# RAM_MUX4_top.net
KiCad netlist of a schematic drawn in Altium Designer
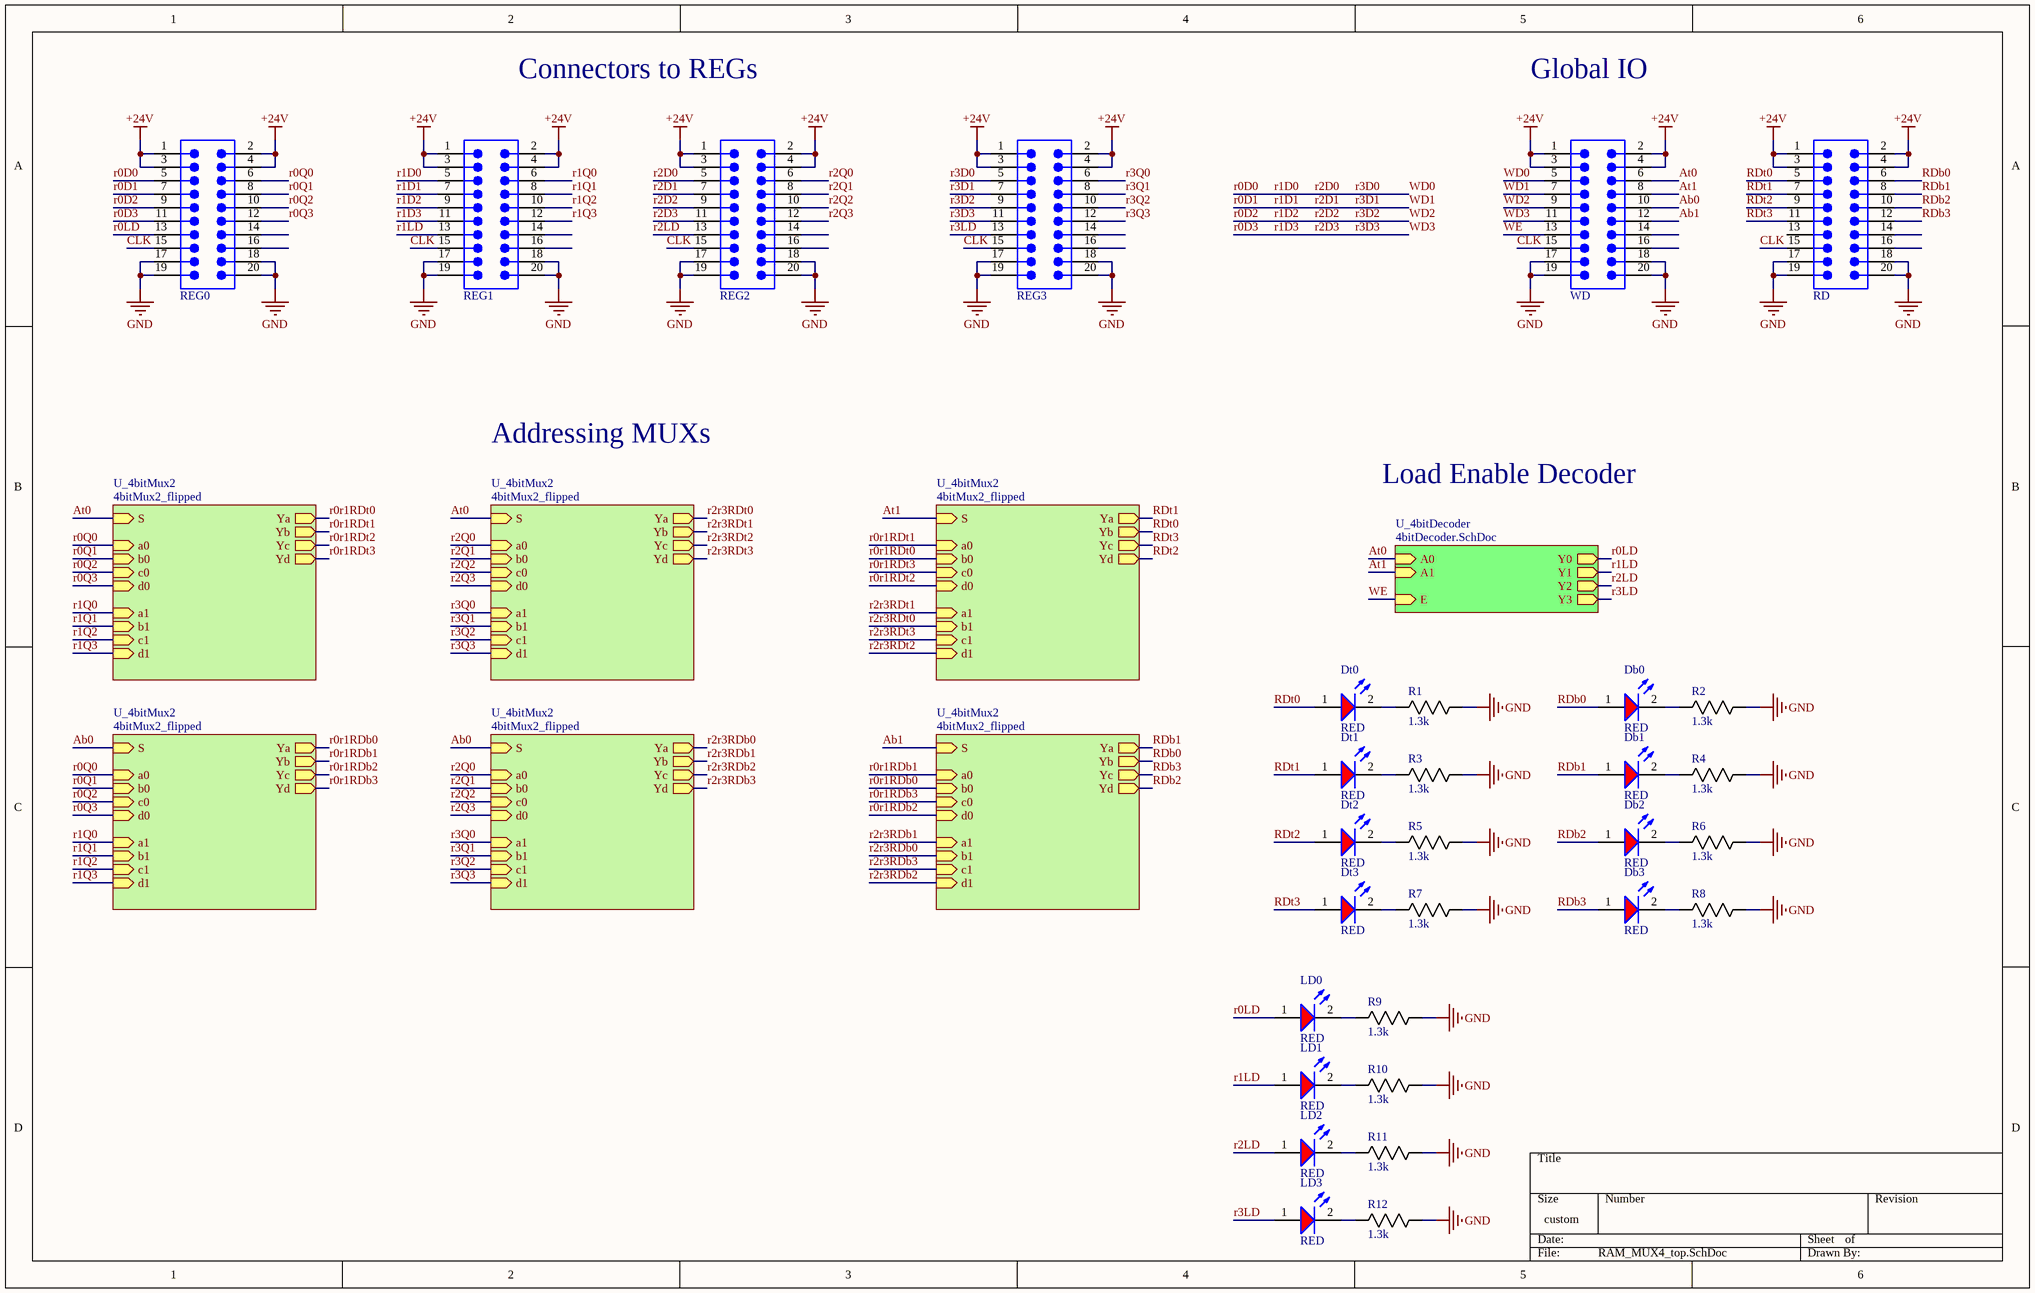
[diagram p0: RAM_MUX4_top.SchDoc]

(export (version "E")
  (design (tool "Eeschema 10.0.6"))
  (components
    (comp (ref "Db0")
      (value "RED")
      (footprint "LED RED 151051RS11000")
      (description "WL-TMRC Red Color Diffused 5 mm Round Through Hole LED")
      (fields
        (field (name "MANUFACTURER") "Wurth Elektronik")
        (field (name "MANUFACTURER PART NUMBER") "151051RS11000")
      )
      (libsource (lib "Schlib1") (part "LED RED 151051RS11000"))
    )
    (comp (ref "Db1")
      (value "RED")
      (footprint "LED RED 151051RS11000")
      (description "WL-TMRC Red Color Diffused 5 mm Round Through Hole LED")
      (fields
        (field (name "MANUFACTURER") "Wurth Elektronik")
        (field (name "MANUFACTURER PART NUMBER") "151051RS11000")
      )
      (libsource (lib "Schlib1") (part "LED RED 151051RS11000"))
    )
    (comp (ref "Db2")
      (value "RED")
      (footprint "LED RED 151051RS11000")
      (description "WL-TMRC Red Color Diffused 5 mm Round Through Hole LED")
      (fields
        (field (name "MANUFACTURER") "Wurth Elektronik")
        (field (name "MANUFACTURER PART NUMBER") "151051RS11000")
      )
      (libsource (lib "Schlib1") (part "LED RED 151051RS11000"))
    )
    (comp (ref "Db3")
      (value "RED")
      (footprint "LED RED 151051RS11000")
      (description "WL-TMRC Red Color Diffused 5 mm Round Through Hole LED")
      (fields
        (field (name "MANUFACTURER") "Wurth Elektronik")
        (field (name "MANUFACTURER PART NUMBER") "151051RS11000")
      )
      (libsource (lib "Schlib1") (part "LED RED 151051RS11000"))
    )
    (comp (ref "Dt0")
      (value "RED")
      (footprint "LED RED 151051RS11000")
      (description "WL-TMRC Red Color Diffused 5 mm Round Through Hole LED")
      (fields
        (field (name "MANUFACTURER") "Wurth Elektronik")
        (field (name "MANUFACTURER PART NUMBER") "151051RS11000")
      )
      (libsource (lib "Schlib1") (part "LED RED 151051RS11000"))
    )
    (comp (ref "Dt1")
      (value "RED")
      (footprint "LED RED 151051RS11000")
      (description "WL-TMRC Red Color Diffused 5 mm Round Through Hole LED")
      (fields
        (field (name "MANUFACTURER") "Wurth Elektronik")
        (field (name "MANUFACTURER PART NUMBER") "151051RS11000")
      )
      (libsource (lib "Schlib1") (part "LED RED 151051RS11000"))
    )
    (comp (ref "Dt2")
      (value "RED")
      (footprint "LED RED 151051RS11000")
      (description "WL-TMRC Red Color Diffused 5 mm Round Through Hole LED")
      (fields
        (field (name "MANUFACTURER") "Wurth Elektronik")
        (field (name "MANUFACTURER PART NUMBER") "151051RS11000")
      )
      (libsource (lib "Schlib1") (part "LED RED 151051RS11000"))
    )
    (comp (ref "Dt3")
      (value "RED")
      (footprint "LED RED 151051RS11000")
      (description "WL-TMRC Red Color Diffused 5 mm Round Through Hole LED")
      (fields
        (field (name "MANUFACTURER") "Wurth Elektronik")
        (field (name "MANUFACTURER PART NUMBER") "151051RS11000")
      )
      (libsource (lib "Schlib1") (part "LED RED 151051RS11000"))
    )
    (comp (ref "LD0")
      (value "RED")
      (footprint "LED RED 151051RS11000")
      (description "WL-TMRC Red Color Diffused 5 mm Round Through Hole LED")
      (fields
        (field (name "MANUFACTURER") "Wurth Elektronik")
        (field (name "MANUFACTURER PART NUMBER") "151051RS11000")
      )
      (libsource (lib "Schlib1") (part "LED RED 151051RS11000"))
    )
    (comp (ref "LD1")
      (value "RED")
      (footprint "LED RED 151051RS11000")
      (description "WL-TMRC Red Color Diffused 5 mm Round Through Hole LED")
      (fields
        (field (name "MANUFACTURER") "Wurth Elektronik")
        (field (name "MANUFACTURER PART NUMBER") "151051RS11000")
      )
      (libsource (lib "Schlib1") (part "LED RED 151051RS11000"))
    )
    (comp (ref "LD2")
      (value "RED")
      (footprint "LED RED 151051RS11000")
      (description "WL-TMRC Red Color Diffused 5 mm Round Through Hole LED")
      (fields
        (field (name "MANUFACTURER") "Wurth Elektronik")
        (field (name "MANUFACTURER PART NUMBER") "151051RS11000")
      )
      (libsource (lib "Schlib1") (part "LED RED 151051RS11000"))
    )
    (comp (ref "LD3")
      (value "RED")
      (footprint "LED RED 151051RS11000")
      (description "WL-TMRC Red Color Diffused 5 mm Round Through Hole LED")
      (fields
        (field (name "MANUFACTURER") "Wurth Elektronik")
        (field (name "MANUFACTURER PART NUMBER") "151051RS11000")
      )
      (libsource (lib "Schlib1") (part "LED RED 151051RS11000"))
    )
    (comp (ref "R1")
      (value "1.3k")
      (footprint "RES 2512")
      (description "Res Thick Film 2512 1.3K Ohm 1% 1W ±100ppm/C Pad SMD Automotive T/R RMCF2512FT1K30")
      (fields
        (field (name "MANUFACTURER") "Stackpole Electronics")
        (field (name "MANUFACTURER PART NUMBER") "RMCF2512FT1K30")
      )
      (libsource (lib "Schlib1") (part "RES 1.3k 2512 1W"))
    )
    (comp (ref "R2")
      (value "1.3k")
      (footprint "RES 2512")
      (description "Res Thick Film 2512 1.3K Ohm 1% 1W ±100ppm/C Pad SMD Automotive T/R RMCF2512FT1K30")
      (fields
        (field (name "MANUFACTURER") "Stackpole Electronics")
        (field (name "MANUFACTURER PART NUMBER") "RMCF2512FT1K30")
      )
      (libsource (lib "Schlib1") (part "RES 1.3k 2512 1W"))
    )
    (comp (ref "R3")
      (value "1.3k")
      (footprint "RES 2512")
      (description "Res Thick Film 2512 1.3K Ohm 1% 1W ±100ppm/C Pad SMD Automotive T/R RMCF2512FT1K30")
      (fields
        (field (name "MANUFACTURER") "Stackpole Electronics")
        (field (name "MANUFACTURER PART NUMBER") "RMCF2512FT1K30")
      )
      (libsource (lib "Schlib1") (part "RES 1.3k 2512 1W"))
    )
    (comp (ref "R4")
      (value "1.3k")
      (footprint "RES 2512")
      (description "Res Thick Film 2512 1.3K Ohm 1% 1W ±100ppm/C Pad SMD Automotive T/R RMCF2512FT1K30")
      (fields
        (field (name "MANUFACTURER") "Stackpole Electronics")
        (field (name "MANUFACTURER PART NUMBER") "RMCF2512FT1K30")
      )
      (libsource (lib "Schlib1") (part "RES 1.3k 2512 1W"))
    )
    (comp (ref "R5")
      (value "1.3k")
      (footprint "RES 2512")
      (description "Res Thick Film 2512 1.3K Ohm 1% 1W ±100ppm/C Pad SMD Automotive T/R RMCF2512FT1K30")
      (fields
        (field (name "MANUFACTURER") "Stackpole Electronics")
        (field (name "MANUFACTURER PART NUMBER") "RMCF2512FT1K30")
      )
      (libsource (lib "Schlib1") (part "RES 1.3k 2512 1W"))
    )
    (comp (ref "R6")
      (value "1.3k")
      (footprint "RES 2512")
      (description "Res Thick Film 2512 1.3K Ohm 1% 1W ±100ppm/C Pad SMD Automotive T/R RMCF2512FT1K30")
      (fields
        (field (name "MANUFACTURER") "Stackpole Electronics")
        (field (name "MANUFACTURER PART NUMBER") "RMCF2512FT1K30")
      )
      (libsource (lib "Schlib1") (part "RES 1.3k 2512 1W"))
    )
    (comp (ref "R7")
      (value "1.3k")
      (footprint "RES 2512")
      (description "Res Thick Film 2512 1.3K Ohm 1% 1W ±100ppm/C Pad SMD Automotive T/R RMCF2512FT1K30")
      (fields
        (field (name "MANUFACTURER") "Stackpole Electronics")
        (field (name "MANUFACTURER PART NUMBER") "RMCF2512FT1K30")
      )
      (libsource (lib "Schlib1") (part "RES 1.3k 2512 1W"))
    )
    (comp (ref "R8")
      (value "1.3k")
      (footprint "RES 2512")
      (description "Res Thick Film 2512 1.3K Ohm 1% 1W ±100ppm/C Pad SMD Automotive T/R RMCF2512FT1K30")
      (fields
        (field (name "MANUFACTURER") "Stackpole Electronics")
        (field (name "MANUFACTURER PART NUMBER") "RMCF2512FT1K30")
      )
      (libsource (lib "Schlib1") (part "RES 1.3k 2512 1W"))
    )
    (comp (ref "R9")
      (value "1.3k")
      (footprint "RES 2512")
      (description "Res Thick Film 2512 1.3K Ohm 1% 1W ±100ppm/C Pad SMD Automotive T/R RMCF2512FT1K30")
      (fields
        (field (name "MANUFACTURER") "Stackpole Electronics")
        (field (name "MANUFACTURER PART NUMBER") "RMCF2512FT1K30")
      )
      (libsource (lib "Schlib1") (part "RES 1.3k 2512 1W"))
    )
    (comp (ref "R10")
      (value "1.3k")
      (footprint "RES 2512")
      (description "Res Thick Film 2512 1.3K Ohm 1% 1W ±100ppm/C Pad SMD Automotive T/R RMCF2512FT1K30")
      (fields
        (field (name "MANUFACTURER") "Stackpole Electronics")
        (field (name "MANUFACTURER PART NUMBER") "RMCF2512FT1K30")
      )
      (libsource (lib "Schlib1") (part "RES 1.3k 2512 1W"))
    )
    (comp (ref "R11")
      (value "1.3k")
      (footprint "RES 2512")
      (description "Res Thick Film 2512 1.3K Ohm 1% 1W ±100ppm/C Pad SMD Automotive T/R RMCF2512FT1K30")
      (fields
        (field (name "MANUFACTURER") "Stackpole Electronics")
        (field (name "MANUFACTURER PART NUMBER") "RMCF2512FT1K30")
      )
      (libsource (lib "Schlib1") (part "RES 1.3k 2512 1W"))
    )
    (comp (ref "R12")
      (value "1.3k")
      (footprint "RES 2512")
      (description "Res Thick Film 2512 1.3K Ohm 1% 1W ±100ppm/C Pad SMD Automotive T/R RMCF2512FT1K30")
      (fields
        (field (name "MANUFACTURER") "Stackpole Electronics")
        (field (name "MANUFACTURER PART NUMBER") "RMCF2512FT1K30")
      )
      (libsource (lib "Schlib1") (part "RES 1.3k 2512 1W"))
    )
    (comp (ref "RD")
      (value "Con 2.54mm 10x2pos")
      (footprint "Con 2.54mm 10x2pos")
      (description "WR-BHD Straight Male, Box Header, Through Hole, 2 Rows, 20 Contacts, 2.54mm Pitch")
      (fields
        (field (name "MANUFACTURER") "Wurth Elektronik")
        (field (name "MANUFACTURER PART NUMBER") "61202021621")
      )
      (libsource (lib "RelayMachine") (part "Con 2.54mm 10x2pos"))
    )
    (comp (ref "REG0")
      (value "Con 2.54mm 10x2pos")
      (footprint "Con 2.54mm 10x2pos")
      (description "WR-BHD Straight Male, Box Header, Through Hole, 2 Rows, 20 Contacts, 2.54mm Pitch")
      (fields
        (field (name "MANUFACTURER") "Wurth Elektronik")
        (field (name "MANUFACTURER PART NUMBER") "61202021621")
      )
      (libsource (lib "RelayMachine") (part "Con 2.54mm 10x2pos"))
    )
    (comp (ref "REG1")
      (value "Con 2.54mm 10x2pos")
      (footprint "Con 2.54mm 10x2pos")
      (description "WR-BHD Straight Male, Box Header, Through Hole, 2 Rows, 20 Contacts, 2.54mm Pitch")
      (fields
        (field (name "MANUFACTURER") "Wurth Elektronik")
        (field (name "MANUFACTURER PART NUMBER") "61202021621")
      )
      (libsource (lib "RelayMachine") (part "Con 2.54mm 10x2pos"))
    )
    (comp (ref "REG2")
      (value "Con 2.54mm 10x2pos")
      (footprint "Con 2.54mm 10x2pos")
      (description "WR-BHD Straight Male, Box Header, Through Hole, 2 Rows, 20 Contacts, 2.54mm Pitch")
      (fields
        (field (name "MANUFACTURER") "Wurth Elektronik")
        (field (name "MANUFACTURER PART NUMBER") "61202021621")
      )
      (libsource (lib "RelayMachine") (part "Con 2.54mm 10x2pos"))
    )
    (comp (ref "REG3")
      (value "Con 2.54mm 10x2pos")
      (footprint "Con 2.54mm 10x2pos")
      (description "WR-BHD Straight Male, Box Header, Through Hole, 2 Rows, 20 Contacts, 2.54mm Pitch")
      (fields
        (field (name "MANUFACTURER") "Wurth Elektronik")
        (field (name "MANUFACTURER PART NUMBER") "61202021621")
      )
      (libsource (lib "RelayMachine") (part "Con 2.54mm 10x2pos"))
    )
    (comp (ref "WD")
      (value "Con 2.54mm 10x2pos")
      (footprint "Con 2.54mm 10x2pos")
      (description "WR-BHD Straight Male, Box Header, Through Hole, 2 Rows, 20 Contacts, 2.54mm Pitch")
      (fields
        (field (name "MANUFACTURER") "Wurth Elektronik")
        (field (name "MANUFACTURER PART NUMBER") "61202021621")
      )
      (libsource (lib "RelayMachine") (part "Con 2.54mm 10x2pos"))
    )
  )
  (nets
    (net (code "1") (name "+24V") (class "Default")
      (node (ref "RD") (pin "1") (pinfunction "1_1") (pintype "passive"))
      (node (ref "RD") (pin "2") (pinfunction "2_2") (pintype "passive"))
      (node (ref "RD") (pin "3") (pinfunction "3_3") (pintype "passive"))
      (node (ref "RD") (pin "4") (pinfunction "4_4") (pintype "passive"))
      (node (ref "REG0") (pin "1") (pinfunction "1_1") (pintype "passive"))
      (node (ref "REG0") (pin "2") (pinfunction "2_2") (pintype "passive"))
      (node (ref "REG0") (pin "3") (pinfunction "3_3") (pintype "passive"))
      (node (ref "REG0") (pin "4") (pinfunction "4_4") (pintype "passive"))
      (node (ref "REG1") (pin "1") (pinfunction "1_1") (pintype "passive"))
      (node (ref "REG1") (pin "2") (pinfunction "2_2") (pintype "passive"))
      (node (ref "REG1") (pin "3") (pinfunction "3_3") (pintype "passive"))
      (node (ref "REG1") (pin "4") (pinfunction "4_4") (pintype "passive"))
      (node (ref "REG2") (pin "1") (pinfunction "1_1") (pintype "passive"))
      (node (ref "REG2") (pin "2") (pinfunction "2_2") (pintype "passive"))
      (node (ref "REG2") (pin "3") (pinfunction "3_3") (pintype "passive"))
      (node (ref "REG2") (pin "4") (pinfunction "4_4") (pintype "passive"))
      (node (ref "REG3") (pin "1") (pinfunction "1_1") (pintype "passive"))
      (node (ref "REG3") (pin "2") (pinfunction "2_2") (pintype "passive"))
      (node (ref "REG3") (pin "3") (pinfunction "3_3") (pintype "passive"))
      (node (ref "REG3") (pin "4") (pinfunction "4_4") (pintype "passive"))
      (node (ref "WD") (pin "1") (pinfunction "1_1") (pintype "passive"))
      (node (ref "WD") (pin "2") (pinfunction "2_2") (pintype "passive"))
      (node (ref "WD") (pin "3") (pinfunction "3_3") (pintype "passive"))
      (node (ref "WD") (pin "4") (pinfunction "4_4") (pintype "passive"))
    )
    (net (code "2") (name "/Ab0") (class "Default")
      (node (ref "WD") (pin "10") (pinfunction "10_10") (pintype "passive"))
    )
    (net (code "3") (name "/Ab1") (class "Default")
      (node (ref "WD") (pin "12") (pinfunction "12_12") (pintype "passive"))
    )
    (net (code "4") (name "/At0") (class "Default")
      (node (ref "WD") (pin "6") (pinfunction "6_6") (pintype "passive"))
    )
    (net (code "5") (name "/At1") (class "Default")
      (node (ref "WD") (pin "8") (pinfunction "8_8") (pintype "passive"))
    )
    (net (code "6") (name "/CLK") (class "Default")
      (node (ref "RD") (pin "15") (pinfunction "15_15") (pintype "passive"))
      (node (ref "REG0") (pin "15") (pinfunction "15_15") (pintype "passive"))
      (node (ref "REG1") (pin "15") (pinfunction "15_15") (pintype "passive"))
      (node (ref "REG2") (pin "15") (pinfunction "15_15") (pintype "passive"))
      (node (ref "REG3") (pin "15") (pinfunction "15_15") (pintype "passive"))
      (node (ref "WD") (pin "15") (pinfunction "15_15") (pintype "passive"))
    )
    (net (code "7") (name "/RDb0") (class "Default")
      (node (ref "Db0") (pin "1") (pinfunction "A_1") (pintype "passive"))
      (node (ref "RD") (pin "6") (pinfunction "6_6") (pintype "passive"))
    )
    (net (code "8") (name "/RDb1") (class "Default")
      (node (ref "Db1") (pin "1") (pinfunction "A_1") (pintype "passive"))
      (node (ref "RD") (pin "8") (pinfunction "8_8") (pintype "passive"))
    )
    (net (code "9") (name "/RDb2") (class "Default")
      (node (ref "Db2") (pin "1") (pinfunction "A_1") (pintype "passive"))
      (node (ref "RD") (pin "10") (pinfunction "10_10") (pintype "passive"))
    )
    (net (code "10") (name "/RDb3") (class "Default")
      (node (ref "Db3") (pin "1") (pinfunction "A_1") (pintype "passive"))
      (node (ref "RD") (pin "12") (pinfunction "12_12") (pintype "passive"))
    )
    (net (code "11") (name "/RDt0") (class "Default")
      (node (ref "Dt0") (pin "1") (pinfunction "A_1") (pintype "passive"))
      (node (ref "RD") (pin "5") (pinfunction "5_5") (pintype "passive"))
    )
    (net (code "12") (name "/RDt1") (class "Default")
      (node (ref "Dt1") (pin "1") (pinfunction "A_1") (pintype "passive"))
      (node (ref "RD") (pin "7") (pinfunction "7_7") (pintype "passive"))
    )
    (net (code "13") (name "/RDt2") (class "Default")
      (node (ref "Dt2") (pin "1") (pinfunction "A_1") (pintype "passive"))
      (node (ref "RD") (pin "9") (pinfunction "9_9") (pintype "passive"))
    )
    (net (code "14") (name "/RDt3") (class "Default")
      (node (ref "Dt3") (pin "1") (pinfunction "A_1") (pintype "passive"))
      (node (ref "RD") (pin "11") (pinfunction "11_11") (pintype "passive"))
    )
    (net (code "15") (name "/WD0") (class "Default")
      (node (ref "REG0") (pin "5") (pinfunction "5_5") (pintype "passive"))
      (node (ref "REG1") (pin "5") (pinfunction "5_5") (pintype "passive"))
      (node (ref "REG2") (pin "5") (pinfunction "5_5") (pintype "passive"))
      (node (ref "REG3") (pin "5") (pinfunction "5_5") (pintype "passive"))
      (node (ref "WD") (pin "5") (pinfunction "5_5") (pintype "passive"))
    )
    (net (code "16") (name "/WD1") (class "Default")
      (node (ref "REG0") (pin "7") (pinfunction "7_7") (pintype "passive"))
      (node (ref "REG1") (pin "7") (pinfunction "7_7") (pintype "passive"))
      (node (ref "REG2") (pin "7") (pinfunction "7_7") (pintype "passive"))
      (node (ref "REG3") (pin "7") (pinfunction "7_7") (pintype "passive"))
      (node (ref "WD") (pin "7") (pinfunction "7_7") (pintype "passive"))
    )
    (net (code "17") (name "/WD2") (class "Default")
      (node (ref "REG0") (pin "9") (pinfunction "9_9") (pintype "passive"))
      (node (ref "REG1") (pin "9") (pinfunction "9_9") (pintype "passive"))
      (node (ref "REG2") (pin "9") (pinfunction "9_9") (pintype "passive"))
      (node (ref "REG3") (pin "9") (pinfunction "9_9") (pintype "passive"))
      (node (ref "WD") (pin "9") (pinfunction "9_9") (pintype "passive"))
    )
    (net (code "18") (name "/WD3") (class "Default")
      (node (ref "REG0") (pin "11") (pinfunction "11_11") (pintype "passive"))
      (node (ref "REG1") (pin "11") (pinfunction "11_11") (pintype "passive"))
      (node (ref "REG2") (pin "11") (pinfunction "11_11") (pintype "passive"))
      (node (ref "REG3") (pin "11") (pinfunction "11_11") (pintype "passive"))
      (node (ref "WD") (pin "11") (pinfunction "11_11") (pintype "passive"))
    )
    (net (code "19") (name "/WE") (class "Default")
      (node (ref "WD") (pin "13") (pinfunction "13_13") (pintype "passive"))
    )
    (net (code "20") (name "/r0LD") (class "Default")
      (node (ref "LD0") (pin "1") (pinfunction "A_1") (pintype "passive"))
      (node (ref "REG0") (pin "13") (pinfunction "13_13") (pintype "passive"))
    )
    (net (code "21") (name "/r0Q0") (class "Default")
      (node (ref "REG0") (pin "6") (pinfunction "6_6") (pintype "passive"))
    )
    (net (code "22") (name "/r0Q1") (class "Default")
      (node (ref "REG0") (pin "8") (pinfunction "8_8") (pintype "passive"))
    )
    (net (code "23") (name "/r0Q2") (class "Default")
      (node (ref "REG0") (pin "10") (pinfunction "10_10") (pintype "passive"))
    )
    (net (code "24") (name "/r0Q3") (class "Default")
      (node (ref "REG0") (pin "12") (pinfunction "12_12") (pintype "passive"))
    )
    (net (code "33") (name "/r1LD") (class "Default")
      (node (ref "LD1") (pin "1") (pinfunction "A_1") (pintype "passive"))
      (node (ref "REG1") (pin "13") (pinfunction "13_13") (pintype "passive"))
    )
    (net (code "34") (name "/r1Q0") (class "Default")
      (node (ref "REG1") (pin "6") (pinfunction "6_6") (pintype "passive"))
    )
    (net (code "35") (name "/r1Q1") (class "Default")
      (node (ref "REG1") (pin "8") (pinfunction "8_8") (pintype "passive"))
    )
    (net (code "36") (name "/r1Q2") (class "Default")
      (node (ref "REG1") (pin "10") (pinfunction "10_10") (pintype "passive"))
    )
    (net (code "37") (name "/r1Q3") (class "Default")
      (node (ref "REG1") (pin "12") (pinfunction "12_12") (pintype "passive"))
    )
    (net (code "38") (name "/r2LD") (class "Default")
      (node (ref "LD2") (pin "1") (pinfunction "A_1") (pintype "passive"))
      (node (ref "REG2") (pin "13") (pinfunction "13_13") (pintype "passive"))
    )
    (net (code "39") (name "/r2Q0") (class "Default")
      (node (ref "REG2") (pin "6") (pinfunction "6_6") (pintype "passive"))
    )
    (net (code "40") (name "/r2Q1") (class "Default")
      (node (ref "REG2") (pin "8") (pinfunction "8_8") (pintype "passive"))
    )
    (net (code "41") (name "/r2Q2") (class "Default")
      (node (ref "REG2") (pin "10") (pinfunction "10_10") (pintype "passive"))
    )
    (net (code "42") (name "/r2Q3") (class "Default")
      (node (ref "REG2") (pin "12") (pinfunction "12_12") (pintype "passive"))
    )
    (net (code "51") (name "/r3LD") (class "Default")
      (node (ref "LD3") (pin "1") (pinfunction "A_1") (pintype "passive"))
      (node (ref "REG3") (pin "13") (pinfunction "13_13") (pintype "passive"))
    )
    (net (code "52") (name "/r3Q0") (class "Default")
      (node (ref "REG3") (pin "6") (pinfunction "6_6") (pintype "passive"))
    )
    (net (code "53") (name "/r3Q1") (class "Default")
      (node (ref "REG3") (pin "8") (pinfunction "8_8") (pintype "passive"))
    )
    (net (code "54") (name "/r3Q2") (class "Default")
      (node (ref "REG3") (pin "10") (pinfunction "10_10") (pintype "passive"))
    )
    (net (code "55") (name "/r3Q3") (class "Default")
      (node (ref "REG3") (pin "12") (pinfunction "12_12") (pintype "passive"))
    )
    (net (code "56") (name "GND") (class "Default")
      (node (ref "R1") (pin "2") (pinfunction "2_2") (pintype "passive"))
      (node (ref "R10") (pin "2") (pinfunction "2_2") (pintype "passive"))
      (node (ref "R11") (pin "2") (pinfunction "2_2") (pintype "passive"))
      (node (ref "R12") (pin "2") (pinfunction "2_2") (pintype "passive"))
      (node (ref "R2") (pin "2") (pinfunction "2_2") (pintype "passive"))
      (node (ref "R3") (pin "2") (pinfunction "2_2") (pintype "passive"))
      (node (ref "R4") (pin "2") (pinfunction "2_2") (pintype "passive"))
      (node (ref "R5") (pin "2") (pinfunction "2_2") (pintype "passive"))
      (node (ref "R6") (pin "2") (pinfunction "2_2") (pintype "passive"))
      (node (ref "R7") (pin "2") (pinfunction "2_2") (pintype "passive"))
      (node (ref "R8") (pin "2") (pinfunction "2_2") (pintype "passive"))
      (node (ref "R9") (pin "2") (pinfunction "2_2") (pintype "passive"))
      (node (ref "RD") (pin "17") (pinfunction "17_17") (pintype "passive"))
      (node (ref "RD") (pin "18") (pinfunction "18_18") (pintype "passive"))
      (node (ref "RD") (pin "19") (pinfunction "19_19") (pintype "passive"))
      (node (ref "RD") (pin "20") (pinfunction "20_20") (pintype "passive"))
      (node (ref "REG0") (pin "17") (pinfunction "17_17") (pintype "passive"))
      (node (ref "REG0") (pin "18") (pinfunction "18_18") (pintype "passive"))
      (node (ref "REG0") (pin "19") (pinfunction "19_19") (pintype "passive"))
      (node (ref "REG0") (pin "20") (pinfunction "20_20") (pintype "passive"))
      (node (ref "REG1") (pin "17") (pinfunction "17_17") (pintype "passive"))
      (node (ref "REG1") (pin "18") (pinfunction "18_18") (pintype "passive"))
      (node (ref "REG1") (pin "19") (pinfunction "19_19") (pintype "passive"))
      (node (ref "REG1") (pin "20") (pinfunction "20_20") (pintype "passive"))
      (node (ref "REG2") (pin "17") (pinfunction "17_17") (pintype "passive"))
      (node (ref "REG2") (pin "18") (pinfunction "18_18") (pintype "passive"))
      (node (ref "REG2") (pin "19") (pinfunction "19_19") (pintype "passive"))
      (node (ref "REG2") (pin "20") (pinfunction "20_20") (pintype "passive"))
      (node (ref "REG3") (pin "17") (pinfunction "17_17") (pintype "passive"))
      (node (ref "REG3") (pin "18") (pinfunction "18_18") (pintype "passive"))
      (node (ref "REG3") (pin "19") (pinfunction "19_19") (pintype "passive"))
      (node (ref "REG3") (pin "20") (pinfunction "20_20") (pintype "passive"))
      (node (ref "WD") (pin "17") (pinfunction "17_17") (pintype "passive"))
      (node (ref "WD") (pin "18") (pinfunction "18_18") (pintype "passive"))
      (node (ref "WD") (pin "19") (pinfunction "19_19") (pintype "passive"))
      (node (ref "WD") (pin "20") (pinfunction "20_20") (pintype "passive"))
    )
    (net (code "57") (name "Net-(Db0-K)") (class "Default")
      (node (ref "Db0") (pin "2") (pinfunction "K_2") (pintype "passive"))
      (node (ref "R2") (pin "1") (pinfunction "1_1") (pintype "passive"))
    )
    (net (code "58") (name "Net-(Db1-K)") (class "Default")
      (node (ref "Db1") (pin "2") (pinfunction "K_2") (pintype "passive"))
      (node (ref "R4") (pin "1") (pinfunction "1_1") (pintype "passive"))
    )
    (net (code "59") (name "Net-(Db2-K)") (class "Default")
      (node (ref "Db2") (pin "2") (pinfunction "K_2") (pintype "passive"))
      (node (ref "R6") (pin "1") (pinfunction "1_1") (pintype "passive"))
    )
    (net (code "60") (name "Net-(Db3-K)") (class "Default")
      (node (ref "Db3") (pin "2") (pinfunction "K_2") (pintype "passive"))
      (node (ref "R8") (pin "1") (pinfunction "1_1") (pintype "passive"))
    )
    (net (code "61") (name "Net-(Dt0-K)") (class "Default")
      (node (ref "Dt0") (pin "2") (pinfunction "K_2") (pintype "passive"))
      (node (ref "R1") (pin "1") (pinfunction "1_1") (pintype "passive"))
    )
    (net (code "62") (name "Net-(Dt1-K)") (class "Default")
      (node (ref "Dt1") (pin "2") (pinfunction "K_2") (pintype "passive"))
      (node (ref "R3") (pin "1") (pinfunction "1_1") (pintype "passive"))
    )
    (net (code "63") (name "Net-(Dt2-K)") (class "Default")
      (node (ref "Dt2") (pin "2") (pinfunction "K_2") (pintype "passive"))
      (node (ref "R5") (pin "1") (pinfunction "1_1") (pintype "passive"))
    )
    (net (code "64") (name "Net-(Dt3-K)") (class "Default")
      (node (ref "Dt3") (pin "2") (pinfunction "K_2") (pintype "passive"))
      (node (ref "R7") (pin "1") (pinfunction "1_1") (pintype "passive"))
    )
    (net (code "65") (name "Net-(LD0-K)") (class "Default")
      (node (ref "LD0") (pin "2") (pinfunction "K_2") (pintype "passive"))
      (node (ref "R9") (pin "1") (pinfunction "1_1") (pintype "passive"))
    )
    (net (code "66") (name "Net-(LD1-K)") (class "Default")
      (node (ref "LD1") (pin "2") (pinfunction "K_2") (pintype "passive"))
      (node (ref "R10") (pin "1") (pinfunction "1_1") (pintype "passive"))
    )
    (net (code "67") (name "Net-(LD2-K)") (class "Default")
      (node (ref "LD2") (pin "2") (pinfunction "K_2") (pintype "passive"))
      (node (ref "R11") (pin "1") (pinfunction "1_1") (pintype "passive"))
    )
    (net (code "68") (name "Net-(LD3-K)") (class "Default")
      (node (ref "LD3") (pin "2") (pinfunction "K_2") (pintype "passive"))
      (node (ref "R12") (pin "1") (pinfunction "1_1") (pintype "passive"))
    )
    (net (code "69") (name "unconnected-(RD-Pad13)") (class "Default")
      (node (ref "RD") (pin "13") (pinfunction "13_13") (pintype "passive"))
    )
    (net (code "70") (name "unconnected-(RD-Pad14)") (class "Default")
      (node (ref "RD") (pin "14") (pinfunction "14_14") (pintype "passive"))
    )
    (net (code "71") (name "unconnected-(RD-Pad16)") (class "Default")
      (node (ref "RD") (pin "16") (pinfunction "16_16") (pintype "passive"))
    )
    (net (code "72") (name "unconnected-(REG0-Pad14)") (class "Default")
      (node (ref "REG0") (pin "14") (pinfunction "14_14") (pintype "passive"))
    )
    (net (code "73") (name "unconnected-(REG0-Pad16)") (class "Default")
      (node (ref "REG0") (pin "16") (pinfunction "16_16") (pintype "passive"))
    )
    (net (code "74") (name "unconnected-(REG1-Pad14)") (class "Default")
      (node (ref "REG1") (pin "14") (pinfunction "14_14") (pintype "passive"))
    )
    (net (code "75") (name "unconnected-(REG1-Pad16)") (class "Default")
      (node (ref "REG1") (pin "16") (pinfunction "16_16") (pintype "passive"))
    )
    (net (code "76") (name "unconnected-(REG2-Pad14)") (class "Default")
      (node (ref "REG2") (pin "14") (pinfunction "14_14") (pintype "passive"))
    )
    (net (code "77") (name "unconnected-(REG2-Pad16)") (class "Default")
      (node (ref "REG2") (pin "16") (pinfunction "16_16") (pintype "passive"))
    )
    (net (code "78") (name "unconnected-(REG3-Pad14)") (class "Default")
      (node (ref "REG3") (pin "14") (pinfunction "14_14") (pintype "passive"))
    )
    (net (code "79") (name "unconnected-(REG3-Pad16)") (class "Default")
      (node (ref "REG3") (pin "16") (pinfunction "16_16") (pintype "passive"))
    )
    (net (code "80") (name "unconnected-(WD-Pad14)") (class "Default")
      (node (ref "WD") (pin "14") (pinfunction "14_14") (pintype "passive"))
    )
    (net (code "81") (name "unconnected-(WD-Pad16)") (class "Default")
      (node (ref "WD") (pin "16") (pinfunction "16_16") (pintype "passive"))
    )
  )
)
